# WheatstonePrimaryAmplifier.net
KiCad netlist of a schematic drawn in Altium Designer
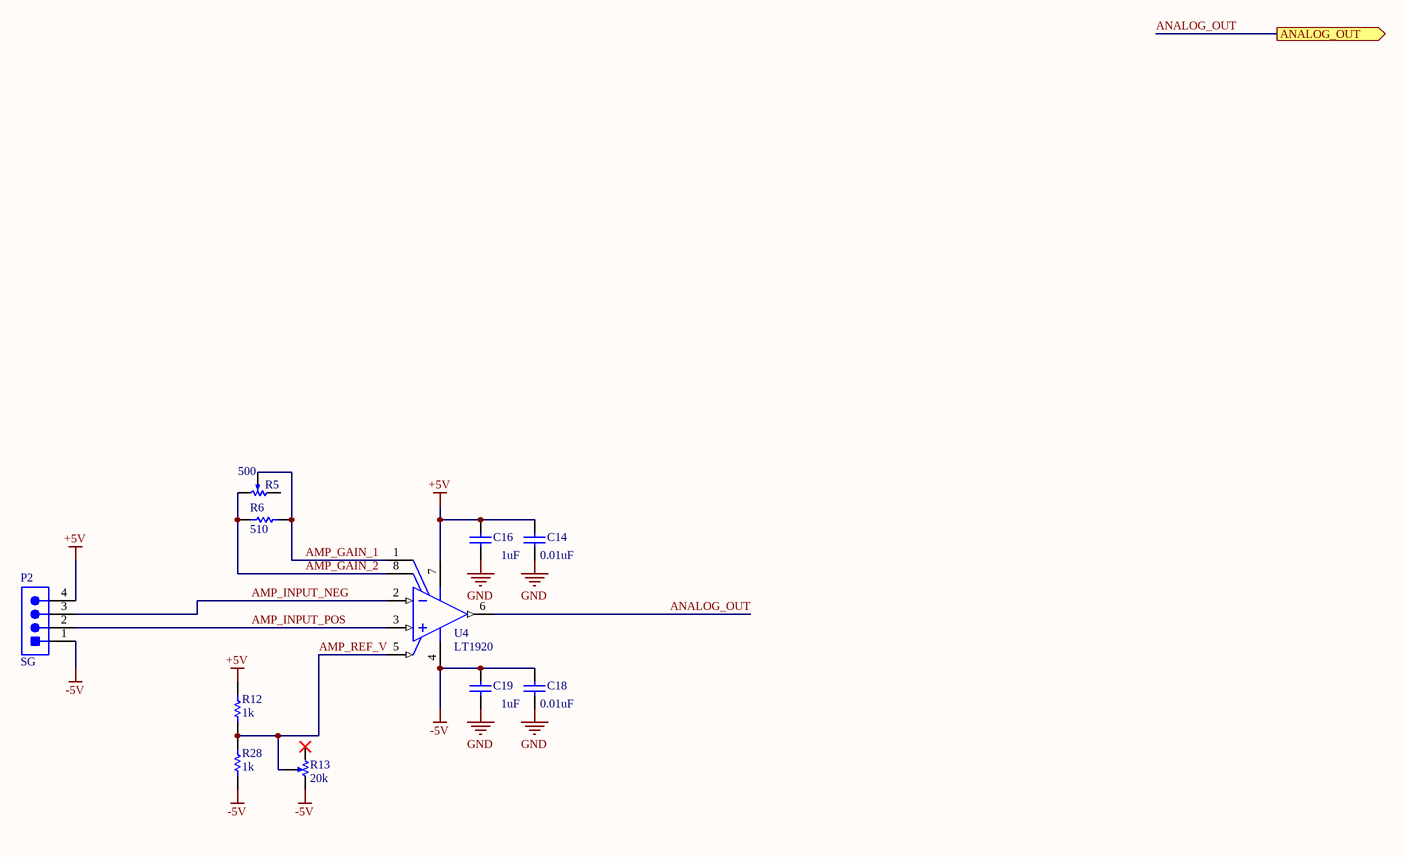
[diagram p0: WheatstonePrimaryAmplifier.SchDoc]

(export (version "E")
  (design (tool "Eeschema 10.0.6"))
  (components
    (comp (ref "C14")
      (value "0.01uF")
      (footprint "1608[0603]")
      (description "Capacitor (Semiconductor SIM Model)")
      (fields (field (name "Comment") "Cap Semi") (field (name "PUBLISHER") "Altium Limited"))
      (libsource (lib "Miscellaneous Devices") (part "Cap Semi"))
    )
    (comp (ref "C16")
      (value "1uF")
      (footprint "1608[0603]")
      (description "Capacitor (Semiconductor SIM Model)")
      (fields (field (name "Comment") "Cap Semi") (field (name "PUBLISHER") "Altium Limited"))
      (libsource (lib "Miscellaneous Devices") (part "Cap Semi"))
    )
    (comp (ref "C18")
      (value "0.01uF")
      (footprint "1608[0603]")
      (description "Capacitor (Semiconductor SIM Model)")
      (fields (field (name "Comment") "Cap Semi") (field (name "PUBLISHER") "Altium Limited"))
      (libsource (lib "Miscellaneous Devices") (part "Cap Semi"))
    )
    (comp (ref "C19")
      (value "1uF")
      (footprint "1608[0603]")
      (description "Capacitor (Semiconductor SIM Model)")
      (fields (field (name "Comment") "Cap Semi") (field (name "PUBLISHER") "Altium Limited"))
      (libsource (lib "Miscellaneous Devices") (part "Cap Semi"))
    )
    (comp (ref "P2")
      (value "SG")
      (footprint "TECO-5-103414-2_V")
      (fields (field (name "MANUFACTURER") "TE Connectivity"))
      (libsource (lib "Altium Content Vault") (part "CN-1P-M-R4"))
    )
    (comp (ref "R5")
      (value "500")
      (footprint "PcbLib1:Trimpot_Cut_tape_3.4x3.4x2")
      (libsource (lib "Schlib1") (part "Component_1"))
    )
    (comp (ref "R6")
      (value "510")
      (footprint "RESC0603(1608)_L")
      (description "510R 0.1W 5% 0603 (1608 Metric)  SMD")
      (fields (field (name "POWER") "0.1 W") (field (name "TOLERANCE") "5 %"))
      (libsource (lib "Altium Content Vault") (part "CMP-1012-00067-1"))
    )
    (comp (ref "R12")
      (value "1k")
      (footprint "RESC1608X55X25ML10T15")
      (description "Chip Resistor, 1 KOhm, +/-1%, 0.1 W, -55 to 155 degC, 0603 (1608 Metric), RoHS, Tape and Reel")
      (libsource (lib "Altium Content Vault") (part "RES-2"))
    )
    (comp (ref "R13")
      (value "20k")
      (footprint "PcbLib1:Trimpot_Cut_tape_3.4x3.4x2")
      (libsource (lib "Schlib1") (part "Component_1"))
    )
    (comp (ref "R28")
      (value "1k")
      (footprint "RESC1608X55X25ML10T15")
      (description "Chip Resistor, 1 KOhm, +/-1%, 0.1 W, -55 to 155 degC, 0603 (1608 Metric), RoHS, Tape and Reel")
      (libsource (lib "Altium Content Vault") (part "RES-2"))
    )
    (comp (ref "U4")
      (value "LT1920")
      (footprint "LT-S8-8_L")
      (fields (field (name "MANUFACTURER") "Linear Technology") (field (name "PARTNUMBER") "LT1920CS8#PBF"))
      (libsource (lib "Altium Content Vault") (part "LT-LT1920-8"))
    )
  )
  (nets
    (net (code "1") (name "+5V") (class "Default")
      (node (ref "C14") (pin "1") (pinfunction "1_1") (pintype "passive"))
      (node (ref "C16") (pin "1") (pinfunction "1_1") (pintype "passive"))
      (node (ref "P2") (pin "4") (pinfunction "4_4") (pintype "passive"))
      (node (ref "R12") (pin "2") (pinfunction "2_2") (pintype "passive"))
      (node (ref "U4") (pin "7") (pinfunction "+VS_7") (pintype "power_in"))
    )
    (net (code "2") (name "-5V") (class "Default")
      (node (ref "C18") (pin "1") (pinfunction "1_1") (pintype "passive"))
      (node (ref "C19") (pin "1") (pinfunction "1_1") (pintype "passive"))
      (node (ref "P2") (pin "1") (pinfunction "1_1") (pintype "passive"))
      (node (ref "R13") (pin "3") (pinfunction "3_3") (pintype "passive"))
      (node (ref "R28") (pin "1") (pinfunction "1_1") (pintype "passive"))
      (node (ref "U4") (pin "4") (pinfunction "-VS_4") (pintype "power_in"))
    )
    (net (code "3") (name "/AMP_GAIN_1") (class "Default")
      (node (ref "R5") (pin "2") (pinfunction "2_2") (pintype "passive"))
      (node (ref "R6") (pin "2") (pinfunction "2_2") (pintype "passive"))
      (node (ref "U4") (pin "1") (pinfunction "RG_1") (pintype "passive"))
    )
    (net (code "4") (name "/AMP_GAIN_2") (class "Default")
      (node (ref "R5") (pin "3") (pinfunction "3_3") (pintype "passive"))
      (node (ref "R6") (pin "1") (pinfunction "1_1") (pintype "passive"))
      (node (ref "U4") (pin "8") (pinfunction "RG_8") (pintype "passive"))
    )
    (net (code "5") (name "/AMP_INPUT_NEG") (class "Default")
      (node (ref "P2") (pin "3") (pinfunction "3_3") (pintype "passive"))
      (node (ref "U4") (pin "2") (pinfunction "-IN_2") (pintype "input"))
    )
    (net (code "6") (name "/AMP_INPUT_POS") (class "Default")
      (node (ref "P2") (pin "2") (pinfunction "2_2") (pintype "passive"))
      (node (ref "U4") (pin "3") (pinfunction "+IN_3") (pintype "input"))
    )
    (net (code "7") (name "/AMP_REF_V") (class "Default")
      (node (ref "R12") (pin "1") (pinfunction "1_1") (pintype "passive"))
      (node (ref "R13") (pin "2") (pinfunction "2_2") (pintype "passive"))
      (node (ref "R28") (pin "2") (pinfunction "2_2") (pintype "passive"))
      (node (ref "U4") (pin "5") (pinfunction "REF_5") (pintype "input"))
    )
    (net (code "8") (name "/ANALOG_OUT") (class "Default")
      (node (ref "U4") (pin "6") (pinfunction "OUTPUT_6") (pintype "output"))
    )
    (net (code "9") (name "GND") (class "Default")
      (node (ref "C14") (pin "2") (pinfunction "2_2") (pintype "passive"))
      (node (ref "C16") (pin "2") (pinfunction "2_2") (pintype "passive"))
      (node (ref "C18") (pin "2") (pinfunction "2_2") (pintype "passive"))
      (node (ref "C19") (pin "2") (pinfunction "2_2") (pintype "passive"))
    )
    (net (code "10") (name "unconnected-(R5-Pad1)") (class "Default")
      (node (ref "R5") (pin "1") (pinfunction "1_1") (pintype "passive"))
    )
    (net (code "11") (name "unconnected-(R13-Pad1)") (class "Default")
      (node (ref "R13") (pin "1") (pinfunction "1_1") (pintype "passive+no_connect"))
    )
  )
)
